# Driver_Controller.net
KiCad netlist of a schematic drawn in Altium Designer
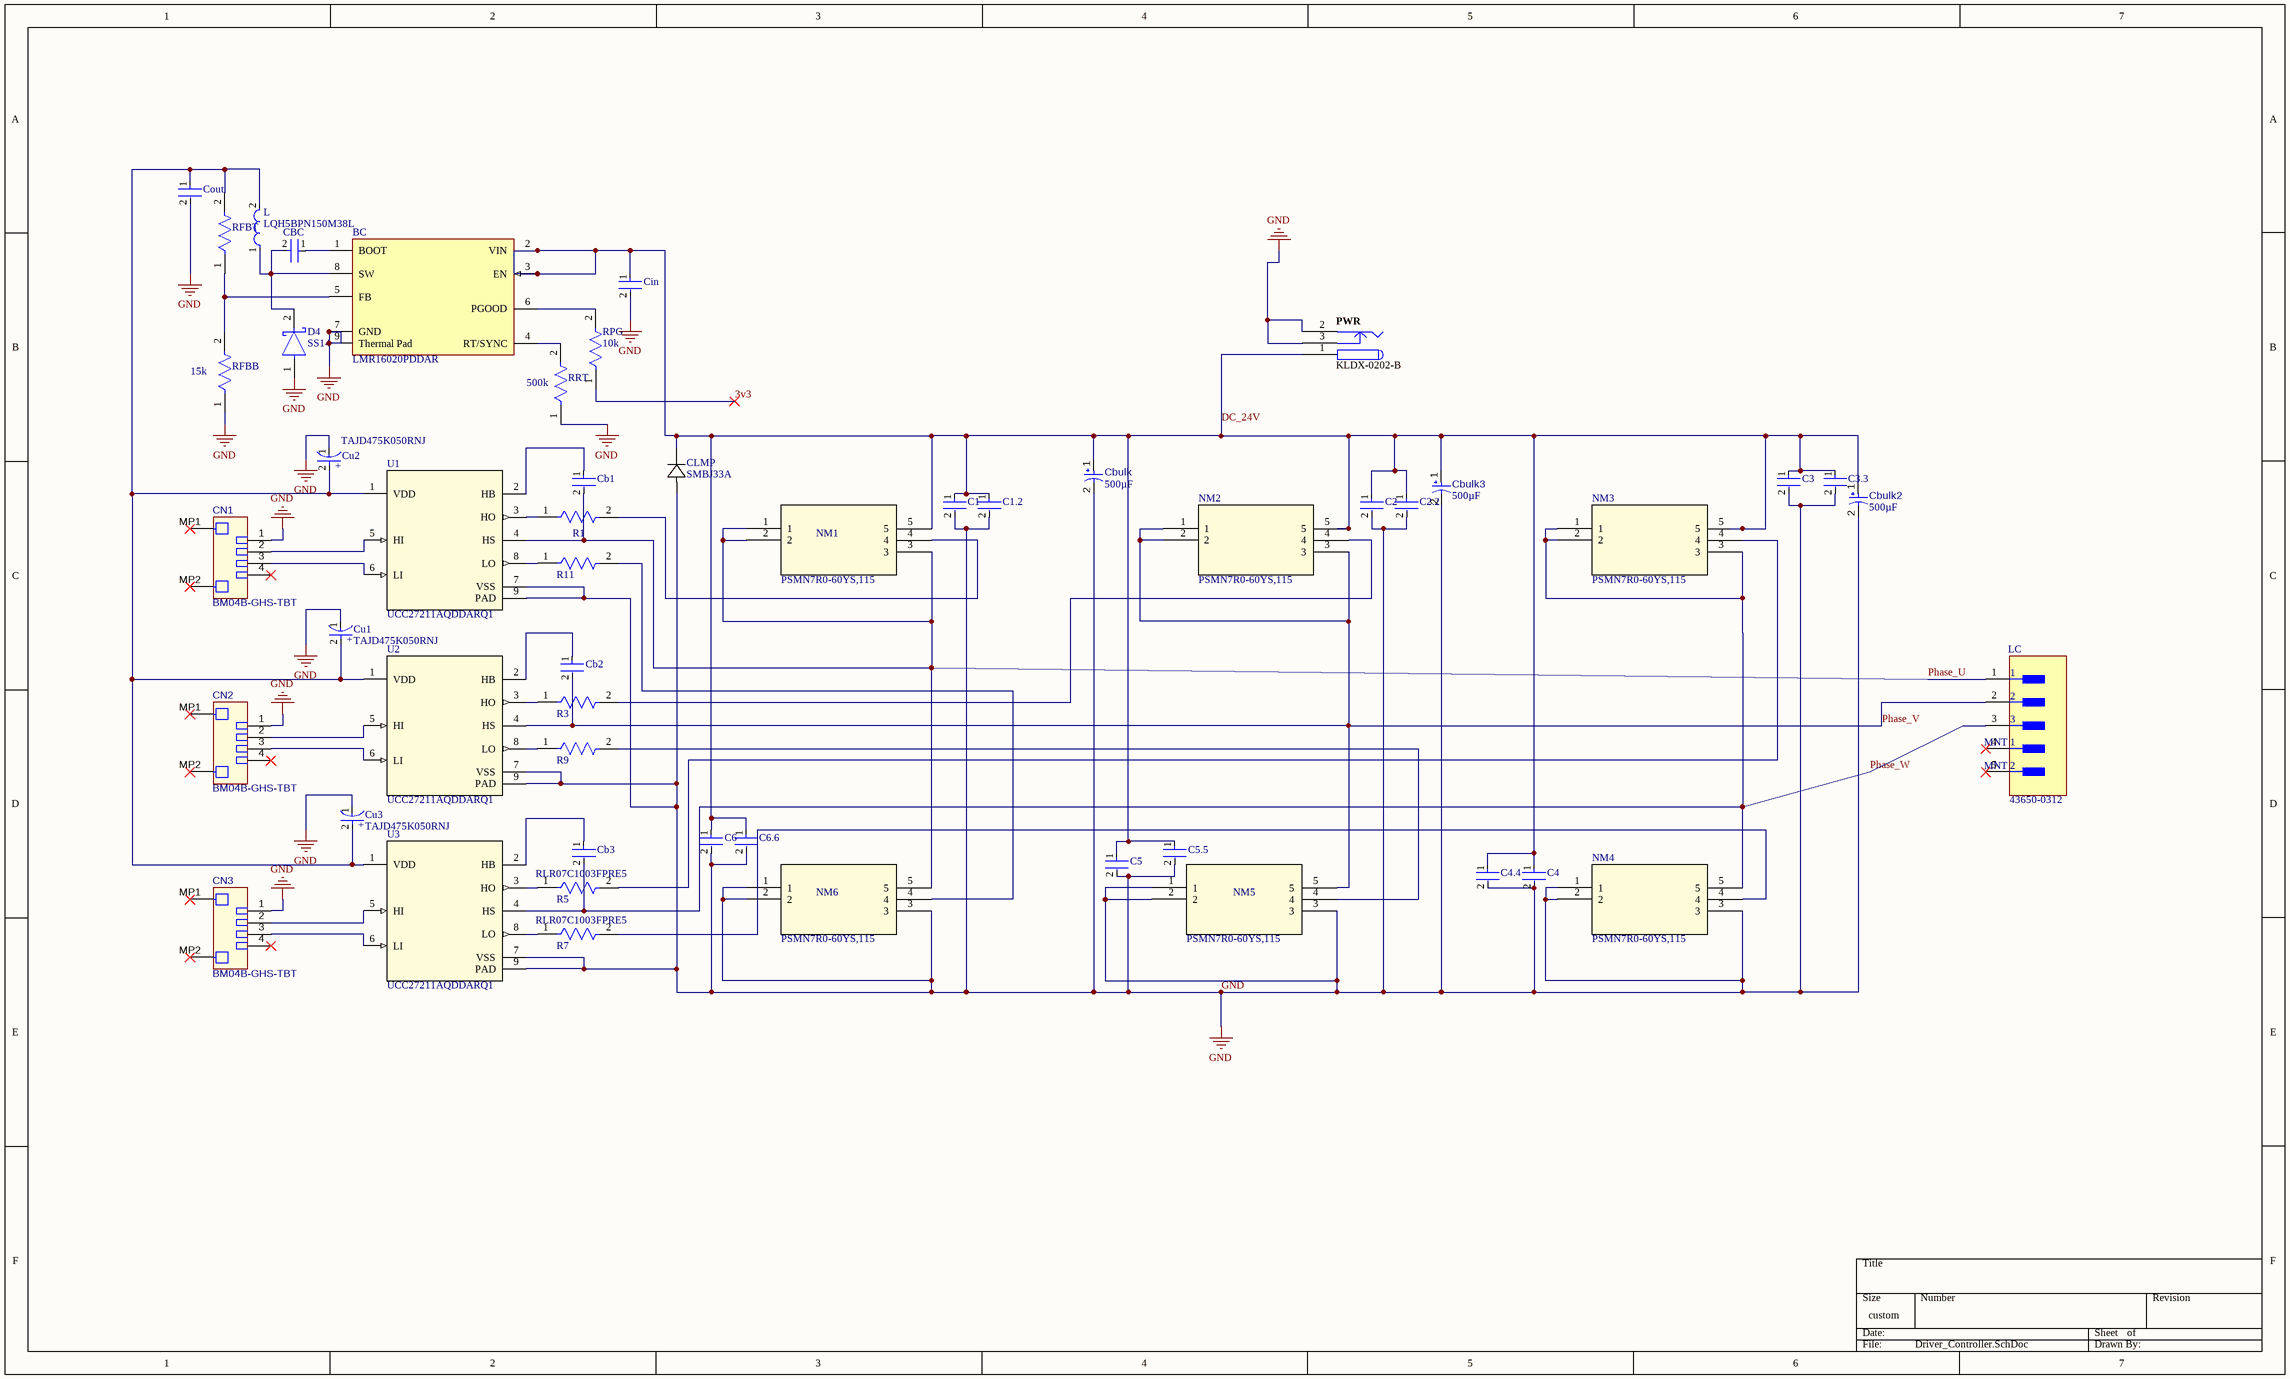
[diagram p0: Driver_Controller.SchDoc]

(export (version "E")
  (design (tool "Eeschema 10.0.6"))
  (components
    (comp (ref "BC")
      (value "LMR16020PDDAR")
      (footprint "FP-DDA0008E-MFG")
      (description "IC REG BUCK ADJUSTABLE 2A 8SOPWR")
      (fields
        (field (name "OCTOPART") "https://octopart.com/lmr16020pddar-texas+instruments-70110951")
        (field (name "MANUFACTURER") "Texas Instruments")
      )
      (libsource (lib "Altium Content Vault") (part "f39d125abe64159f813db9a9ec740f7"))
    )
    (comp (ref "C1")
      (value "RCER72A104K1K1H03B")
      (footprint "FP-RCE1K1-2_5-MFG")
      (description "1uF")
      (fields (field (name "TOLERANCE") "10%"))
      (libsource (lib "") (part "02cd4be3c70576c341d710602a673aa_1"))
    )
    (comp (ref "C1.2")
      (value "RCER72A104K1K1H03B")
      (footprint "FP-RCE1K1-2_5-MFG")
      (description "Cap Ceramic Monolithic 100nF 100V 10% Thru-Hole Bulk")
      (fields (field (name "TOLERANCE") "10%"))
      (libsource (lib "") (part "02cd4be3c70576c341d710602a673aa_1"))
    )
    (comp (ref "C2")
      (value "RCER72A104K1K1H03B")
      (footprint "FP-RCE1K1-2_5-MFG")
      (description "Cap Ceramic Monolithic 100nF 100V 10% Thru-Hole Bulk")
      (fields (field (name "TOLERANCE") "10%"))
      (libsource (lib "") (part "02cd4be3c70576c341d710602a673aa_1"))
    )
    (comp (ref "C2.2")
      (value "RCER72A104K1K1H03B")
      (footprint "FP-RCE1K1-2_5-MFG")
      (description "Cap Ceramic Monolithic 100nF 100V 10% Thru-Hole Bulk")
      (fields (field (name "TOLERANCE") "10%"))
      (libsource (lib "") (part "02cd4be3c70576c341d710602a673aa_1"))
    )
    (comp (ref "C3")
      (value "RCER72A104K1K1H03B")
      (footprint "FP-RCE1K1-2_5-MFG")
      (description "Cap Ceramic Monolithic 100nF 100V 10% Thru-Hole Bulk")
      (fields (field (name "TOLERANCE") "10%"))
      (libsource (lib "") (part "02cd4be3c70576c341d710602a673aa_1"))
    )
    (comp (ref "C3.3")
      (value "RCER72A104K1K1H03B")
      (footprint "FP-RCE1K1-2_5-MFG")
      (description "Cap Ceramic Monolithic 100nF 100V 10% Thru-Hole Bulk")
      (fields (field (name "TOLERANCE") "10%"))
      (libsource (lib "") (part "02cd4be3c70576c341d710602a673aa_1"))
    )
    (comp (ref "C4")
      (value "RCER72A104K1K1H03B")
      (footprint "FP-RCE1K1-2_5-MFG")
      (description "Cap Ceramic Monolithic 100nF 100V 10% Thru-Hole Bulk")
      (fields (field (name "TOLERANCE") "10%"))
      (libsource (lib "") (part "02cd4be3c70576c341d710602a673aa_1"))
    )
    (comp (ref "C4.4")
      (value "RCER72A104K1K1H03B")
      (footprint "FP-RCE1K1-2_5-MFG")
      (description "Cap Ceramic Monolithic 100nF 100V 10% Thru-Hole Bulk")
      (fields (field (name "TOLERANCE") "10%"))
      (libsource (lib "") (part "02cd4be3c70576c341d710602a673aa_1"))
    )
    (comp (ref "C5")
      (value "RCER72A104K1K1H03B")
      (footprint "FP-RCE1K1-2_5-MFG")
      (description "Cap Ceramic Monolithic 100nF 100V 10% Thru-Hole Bulk")
      (fields (field (name "TOLERANCE") "10%"))
      (libsource (lib "") (part "02cd4be3c70576c341d710602a673aa_1"))
    )
    (comp (ref "C5.5")
      (value "RCER72A104K1K1H03B")
      (footprint "FP-RCE1K1-2_5-MFG")
      (description "Cap Ceramic Monolithic 100nF 100V 10% Thru-Hole Bulk")
      (fields (field (name "TOLERANCE") "10%"))
      (libsource (lib "") (part "02cd4be3c70576c341d710602a673aa_1"))
    )
    (comp (ref "C6")
      (value "RCER72A104K1K1H03B")
      (footprint "FP-RCE1K1-2_5-MFG")
      (description "Cap Ceramic Monolithic 100nF 100V 10% Thru-Hole Bulk")
      (fields (field (name "TOLERANCE") "10%"))
      (libsource (lib "") (part "02cd4be3c70576c341d710602a673aa_1"))
    )
    (comp (ref "C6.6")
      (value "RCER72A104K1K1H03B")
      (footprint "FP-RCE1K1-2_5-MFG")
      (description "Cap Ceramic Monolithic 100nF 100V 10% Thru-Hole Bulk")
      (fields (field (name "TOLERANCE") "10%"))
      (libsource (lib "") (part "02cd4be3c70576c341d710602a673aa_1"))
    )
    (comp (ref "Cb1")
      (value "RCER72A104K1K1H03B")
      (footprint "FP-RCE1K1-2_5-MFG")
      (description "0.22uF")
      (fields (field (name "TOLERANCE") "10%"))
      (libsource (lib "") (part "02cd4be3c70576c341d710602a673aa_1"))
    )
    (comp (ref "Cb2")
      (value "RCER72A104K1K1H03B")
      (footprint "FP-RCE1K1-2_5-MFG")
      (description "Cap Ceramic Monolithic 100nF 100V 10% Thru-Hole Bulk")
      (fields (field (name "TOLERANCE") "10%"))
      (libsource (lib "") (part "02cd4be3c70576c341d710602a673aa_1"))
    )
    (comp (ref "Cb3")
      (value "RCER72A104K1K1H03B")
      (footprint "FP-RCE1K1-2_5-MFG")
      (description "Cap Ceramic Monolithic 100nF 100V 10% Thru-Hole Bulk")
      (fields (field (name "TOLERANCE") "10%"))
      (libsource (lib "") (part "02cd4be3c70576c341d710602a673aa_1"))
    )
    (comp (ref "CBC")
      (value "RCER72A104K1K1H03B")
      (footprint "FP-RCE1K1-2_5-MFG")
      (description "0.1 uF cermaic")
      (fields (field (name "TOLERANCE") "10%"))
      (libsource (lib "Altium Content Vault") (part "02cd4be3c70576c341d710602a673aa"))
    )
    (comp (ref "Cbulk")
      (value "500µF")
      (footprint "CAPPR55-200-1100X500X1200")
      (description "220 uF electrolytic capacitor 50V")
      (fields (field (name "TOLERANCE") "20%") (field (name "MANUFACTURER") "Panasonic"))
      (libsource (lib "St121903 St121903") (part "CAP-P-2"))
    )
    (comp (ref "Cbulk2")
      (value "500µF")
      (footprint "CAPPR55-200-1100X500X1200")
      (description "Aluminum Electrolytic Capacitor, 2.2 uF, +/- 20%, 50 V, -40 to 85 degC, 2-Pin THD, RoHS, Bulk")
      (fields (field (name "TOLERANCE") "20%") (field (name "MANUFACTURER") "Panasonic"))
      (libsource (lib "St121903 St121903") (part "CAP-P-2"))
    )
    (comp (ref "Cbulk3")
      (value "500µF")
      (footprint "CAPPR55-200-1100X500X1200")
      (description "Aluminum Electrolytic Capacitor, 2.2 uF, +/- 20%, 50 V, -40 to 85 degC, 2-Pin THD, RoHS, Bulk")
      (fields (field (name "TOLERANCE") "20%") (field (name "MANUFACTURER") "Panasonic"))
      (libsource (lib "St121903 St121903") (part "CAP-P-2"))
    )
    (comp (ref "Cin")
      (value "RCER72A104K1K1H03B")
      (footprint "FP-RCE1K1-2_5-MFG")
      (description "10uF")
      (fields (field (name "TOLERANCE") "10%"))
      (libsource (lib "") (part "02cd4be3c70576c341d710602a673aa_1"))
    )
    (comp (ref "CLMP")
      (value "SMBJ33A")
      (footprint "SMB")
      (description "No Description Available")
      (fields (field (name "COPYRIGHT") "Copyright (C) 2025 Ultra Librarian. All rights reserved."))
      (libsource (lib "SMBJ33A") (part "SMBJ33A"))
    )
    (comp (ref "CN1")
      (value "BM04B-GHS-TBT")
      (footprint "JST-BM04B-GHS-TBT_V")
      (description "Header, Pitch 1.25 mm, 1 x 4 Position, Height 4.05 mm, -25 to 85 degC")
      (libsource (lib "St121903 St121903") (part "CMP-00071-3"))
    )
    (comp (ref "CN2")
      (value "BM04B-GHS-TBT")
      (footprint "JST-BM04B-GHS-TBT_V")
      (description "Header, Pitch 1.25 mm, 1 x 4 Position, Height 4.05 mm, -25 to 85 degC")
      (libsource (lib "St121903 St121903") (part "CMP-00071-3"))
    )
    (comp (ref "CN3")
      (value "BM04B-GHS-TBT")
      (footprint "JST-BM04B-GHS-TBT_V")
      (description "Header, Pitch 1.25 mm, 1 x 4 Position, Height 4.05 mm, -25 to 85 degC")
      (libsource (lib "St121903 St121903") (part "CMP-00071-3"))
    )
    (comp (ref "Cout")
      (value "RCER72A104K1K1H03B")
      (footprint "FP-RCE1K1-2_5-MFG")
      (description "47 uF cap")
      (fields (field (name "TOLERANCE") "10%"))
      (libsource (lib "") (part "02cd4be3c70576c341d710602a673aa_1"))
    )
    (comp (ref "Cu1")
      (value "TAJD475K050RNJ")
      (footprint "FP-TAJD-MFG")
      (description "4.7uF 50V  ±10% 1.4Ω 2917  SMD Tantalum Capacitor")
      (fields (field (name "TOLERANCE") "10%") (field (name "VOLTAGE") "50V"))
      (libsource (lib "Altium Content Vault") (part "a00bbbee19879c290e62620ae7e47b1"))
    )
    (comp (ref "Cu2")
      (value "TAJD475K050RNJ")
      (footprint "FP-TAJD-MFG")
      (description "4.7uF 50V  ±10% 1.4Ω 2917  SMD Tantalum Capacitor")
      (fields (field (name "TOLERANCE") "10%") (field (name "VOLTAGE") "50V"))
      (libsource (lib "Altium Content Vault") (part "a00bbbee19879c290e62620ae7e47b1"))
    )
    (comp (ref "Cu3")
      (value "TAJD475K050RNJ")
      (footprint "FP-TAJD-MFG")
      (description "4.7uF 50V  ±10% 1.4Ω 2917  SMD Tantalum Capacitor")
      (fields (field (name "TOLERANCE") "10%") (field (name "VOLTAGE") "50V"))
      (libsource (lib "Altium Content Vault") (part "a00bbbee19879c290e62620ae7e47b1"))
    )
    (comp (ref "D4")
      (value "SS14")
      (footprint "FP-403AE-MFG")
      (description "DIODE SCHOTTKY 40V 1A SMA")
      (fields
        (field (name "MANUFACTURER") "ON Semiconductor")
        (field (name "OCTOPART") "https://octopart.com/ss14-on+semiconductor-29205033")
      )
      (libsource (lib "Altium Content Vault") (part "360ad2f4ac25a952324d13796385471"))
    )
    (comp (ref "L")
      (value "LQH5BPN150M38L")
      (footprint "FP-LQH5BPN_38-MFG")
      (description "Wire Wound Ferrite Inductor for Power Lines 15μH ±20% 0.096Ω 1900mA 2020")
      (libsource (lib "Altium Content Vault") (part "725321dda6339637d4d059423bc1c3c"))
    )
    (comp (ref "LC")
      (value "43650-0312")
      (footprint "FP-43650-0312-MFG")
      (description "CONN HEADER SMD R/A 3POS 3MM")
      (fields
        (field (name "MANUFACTURER") "Molex")
        (field (name "OCTOPART") "https://octopart.com/43650-0312-molex-298103")
      )
      (libsource (lib "Altium Content Vault") (part "793d9f4ef75ba7bed6a6e310629fedb"))
    )
    (comp (ref "NM1")
      (value "PSMN7R0-60YS,115")
      (footprint "IC5_PSMN7R0-60YS,115_NEX-L")
      (description "No Description Available")
      (fields (field (name "COPYRIGHT") "Copyright (C) 2025 Ultra Librarian. All rights reserved."))
      (libsource (lib "PSMN7R0-60YS,115") (part "PSMN7R0-60YS,115"))
    )
    (comp (ref "NM2")
      (value "PSMN7R0-60YS,115")
      (footprint "IC5_PSMN7R0-60YS,115_NEX-L")
      (description "No Description Available")
      (fields (field (name "COPYRIGHT") "Copyright (C) 2025 Ultra Librarian. All rights reserved."))
      (libsource (lib "PSMN7R0-60YS,115") (part "PSMN7R0-60YS,115"))
    )
    (comp (ref "NM3")
      (value "PSMN7R0-60YS,115")
      (footprint "IC5_PSMN7R0-60YS,115_NEX-L")
      (description "No Description Available")
      (fields (field (name "COPYRIGHT") "Copyright (C) 2025 Ultra Librarian. All rights reserved."))
      (libsource (lib "PSMN7R0-60YS,115") (part "PSMN7R0-60YS,115"))
    )
    (comp (ref "NM4")
      (value "PSMN7R0-60YS,115")
      (footprint "IC5_PSMN7R0-60YS,115_NEX-L")
      (description "No Description Available")
      (fields (field (name "COPYRIGHT") "Copyright (C) 2025 Ultra Librarian. All rights reserved."))
      (libsource (lib "PSMN7R0-60YS,115") (part "PSMN7R0-60YS,115"))
    )
    (comp (ref "NM5")
      (value "PSMN7R0-60YS,115")
      (footprint "IC5_PSMN7R0-60YS,115_NEX-L")
      (description "No Description Available")
      (fields (field (name "COPYRIGHT") "Copyright (C) 2025 Ultra Librarian. All rights reserved."))
      (libsource (lib "PSMN7R0-60YS,115") (part "PSMN7R0-60YS,115"))
    )
    (comp (ref "NM6")
      (value "PSMN7R0-60YS,115")
      (footprint "IC5_PSMN7R0-60YS,115_NEX-L")
      (description "No Description Available")
      (fields (field (name "COPYRIGHT") "Copyright (C) 2025 Ultra Librarian. All rights reserved."))
      (libsource (lib "PSMN7R0-60YS,115") (part "PSMN7R0-60YS,115"))
    )
    (comp (ref "PWR")
      (value "KLDX-0202-B")
      (footprint "KYCN-KLDX-0202-B_V")
      (description "3 Conductor Power Jack, 2 break 2 aux contacts")
      (libsource (lib "Altium Content Vault") (part "KYCN-KLDX-0202-B-3"))
    )
    (comp (ref "R1")
      (value "RLR07C1003FPRE5")
      (footprint "FP-RLR07-MFG")
      (description "RLR07C1003FPRE5 Resistor, 100 kOhm, ± 1%, 250 mW, Axial Leaded, Metal Film, Military Reliability")
      (fields (field (name "TOLERANCE") "1%"))
      (libsource (lib "Altium Content Vault") (part "1029c3af85768c4190bb7ad29bc67b5"))
    )
    (comp (ref "R3")
      (value "RLR07C1003FPRE5")
      (footprint "FP-RLR07-MFG")
      (description "RLR07C1003FPRE5 Resistor, 100 kOhm, ± 1%, 250 mW, Axial Leaded, Metal Film, Military Reliability")
      (fields (field (name "TOLERANCE") "1%"))
      (libsource (lib "Altium Content Vault") (part "1029c3af85768c4190bb7ad29bc67b5"))
    )
    (comp (ref "R5")
      (value "RLR07C1003FPRE5")
      (footprint "FP-RLR07-MFG")
      (description "RLR07C1003FPRE5 Resistor, 100 kOhm, ± 1%, 250 mW, Axial Leaded, Metal Film, Military Reliability")
      (fields (field (name "TOLERANCE") "1%"))
      (libsource (lib "Altium Content Vault") (part "1029c3af85768c4190bb7ad29bc67b5"))
    )
    (comp (ref "R7")
      (value "RLR07C1003FPRE5")
      (footprint "FP-RLR07-MFG")
      (description "RLR07C1003FPRE5 Resistor, 100 kOhm, ± 1%, 250 mW, Axial Leaded, Metal Film, Military Reliability")
      (fields (field (name "TOLERANCE") "1%"))
      (libsource (lib "Altium Content Vault") (part "1029c3af85768c4190bb7ad29bc67b5"))
    )
    (comp (ref "R9")
      (value "RLR07C1003FPRE5")
      (footprint "FP-RLR07-MFG")
      (description "RLR07C1003FPRE5 Resistor, 100 kOhm, ± 1%, 250 mW, Axial Leaded, Metal Film, Military Reliability")
      (fields (field (name "TOLERANCE") "1%"))
      (libsource (lib "Altium Content Vault") (part "1029c3af85768c4190bb7ad29bc67b5"))
    )
    (comp (ref "R11")
      (value "RLR07C1003FPRE5")
      (footprint "FP-RLR07-MFG")
      (description "10")
      (fields (field (name "TOLERANCE") "1%"))
      (libsource (lib "Altium Content Vault") (part "1029c3af85768c4190bb7ad29bc67b5"))
    )
    (comp (ref "RFBB")
      (value "15k")
      (footprint "FP-RLR07-MFG")
      (description "RLR07C1003FPRE5 Resistor, 100 kOhm, ± 1%, 250 mW, Axial Leaded, Metal Film, Military Reliability")
      (fields (field (name "TOLERANCE") "1%"))
      (libsource (lib "Altium Content Vault") (part "1029c3af85768c4190bb7ad29bc67b5"))
    )
    (comp (ref "RFBT")
      (value "150k")
      (footprint "FP-RLR07-MFG")
      (description "RLR07C1003FPRE5 Resistor, 100 kOhm, ± 1%, 250 mW, Axial Leaded, Metal Film, Military Reliability")
      (fields (field (name "TOLERANCE") "1%"))
      (libsource (lib "Altium Content Vault") (part "1029c3af85768c4190bb7ad29bc67b5"))
    )
    (comp (ref "RPG")
      (value "10k")
      (footprint "FP-RLR07-MFG")
      (description "RLR07C1003FPRE5 Resistor, 100 kOhm, ± 1%, 250 mW, Axial Leaded, Metal Film, Military Reliability")
      (fields (field (name "TOLERANCE") "1%"))
      (libsource (lib "Altium Content Vault") (part "1029c3af85768c4190bb7ad29bc67b5"))
    )
    (comp (ref "RRT")
      (value "500k")
      (footprint "FP-RLR07-MFG")
      (description "RLR07C1003FPRE5 Resistor, 100 kOhm, ± 1%, 250 mW, Axial Leaded, Metal Film, Military Reliability")
      (fields (field (name "TOLERANCE") "1%"))
      (libsource (lib "Altium Content Vault") (part "1029c3af85768c4190bb7ad29bc67b5"))
    )
    (comp (ref "U1")
      (value "UCC27211AQDDARQ1")
      (footprint "DDA0008E_N")
      (fields (field (name "COPYRIGHT") "Copyright (C) 2025 Ultra Librarian. All rights reserved."))
      (libsource (lib "UCC27211AQDDARQ1") (part "UCC27211AQDDARQ1"))
    )
    (comp (ref "U2")
      (value "UCC27211AQDDARQ1")
      (footprint "DDA0008E_N")
      (fields (field (name "COPYRIGHT") "Copyright (C) 2025 Ultra Librarian. All rights reserved."))
      (libsource (lib "UCC27211AQDDARQ1") (part "UCC27211AQDDARQ1"))
    )
    (comp (ref "U3")
      (value "UCC27211AQDDARQ1")
      (footprint "DDA0008E_N")
      (fields (field (name "COPYRIGHT") "Copyright (C) 2025 Ultra Librarian. All rights reserved."))
      (libsource (lib "UCC27211AQDDARQ1") (part "UCC27211AQDDARQ1"))
    )
  )
  (nets
    (net (code "1") (name "/3v3") (class "Default")
      (node (ref "RPG") (pin "1") (pinfunction "1_1") (pintype "passive+no_connect"))
    )
    (net (code "2") (name "/DC_24V") (class "Default")
      (node (ref "BC") (pin "2") (pinfunction "VIN_2") (pintype "power_in"))
      (node (ref "BC") (pin "3") (pinfunction "EN_3") (pintype "input"))
      (node (ref "C1") (pin "1") (pinfunction "1_1") (pintype "passive"))
      (node (ref "C1.2") (pin "1") (pinfunction "1_1") (pintype "passive"))
      (node (ref "C2") (pin "1") (pinfunction "1_1") (pintype "passive"))
      (node (ref "C2.2") (pin "1") (pinfunction "1_1") (pintype "passive"))
      (node (ref "C3") (pin "1") (pinfunction "1_1") (pintype "passive"))
      (node (ref "C3.3") (pin "1") (pinfunction "1_1") (pintype "passive"))
      (node (ref "C4") (pin "1") (pinfunction "1_1") (pintype "passive"))
      (node (ref "C4.4") (pin "1") (pinfunction "1_1") (pintype "passive"))
      (node (ref "C5") (pin "1") (pinfunction "1_1") (pintype "passive"))
      (node (ref "C5.5") (pin "1") (pinfunction "1_1") (pintype "passive"))
      (node (ref "C6") (pin "1") (pinfunction "1_1") (pintype "passive"))
      (node (ref "C6.6") (pin "1") (pinfunction "1_1") (pintype "passive"))
      (node (ref "CLMP") (pin "1") (pinfunction "1_1") (pintype "passive"))
      (node (ref "Cbulk") (pin "1") (pinfunction "1_1") (pintype "passive"))
      (node (ref "Cbulk2") (pin "1") (pinfunction "1_1") (pintype "passive"))
      (node (ref "Cbulk3") (pin "1") (pinfunction "1_1") (pintype "passive"))
      (node (ref "Cin") (pin "1") (pinfunction "1_1") (pintype "passive"))
      (node (ref "NM1") (pin "5") (pinfunction "5_5") (pintype "passive"))
      (node (ref "NM2") (pin "5") (pinfunction "5_5") (pintype "passive"))
      (node (ref "NM3") (pin "5") (pinfunction "5_5") (pintype "passive"))
      (node (ref "PWR") (pin "1") (pintype "power_in"))
    )
    (net (code "3") (name "/Phase_U") (class "Default")
      (node (ref "Cb1") (pin "2") (pinfunction "2_2") (pintype "passive"))
      (node (ref "LC") (pin "1") (pinfunction "1_1") (pintype "passive"))
      (node (ref "NM1") (pin "1") (pinfunction "1_1") (pintype "passive"))
      (node (ref "NM1") (pin "2") (pinfunction "2_2") (pintype "passive"))
      (node (ref "NM1") (pin "3") (pinfunction "3_3") (pintype "passive"))
      (node (ref "NM6") (pin "5") (pinfunction "5_5") (pintype "passive"))
      (node (ref "U1") (pin "4") (pinfunction "HS_4") (pintype "power_in"))
    )
    (net (code "4") (name "/Phase_V") (class "Default")
      (node (ref "Cb2") (pin "2") (pinfunction "2_2") (pintype "passive"))
      (node (ref "LC") (pin "2") (pinfunction "2_2") (pintype "passive"))
      (node (ref "NM2") (pin "1") (pinfunction "1_1") (pintype "passive"))
      (node (ref "NM2") (pin "2") (pinfunction "2_2") (pintype "passive"))
      (node (ref "NM2") (pin "3") (pinfunction "3_3") (pintype "passive"))
      (node (ref "NM5") (pin "5") (pinfunction "5_5") (pintype "passive"))
      (node (ref "U2") (pin "4") (pinfunction "HS_4") (pintype "power_in"))
    )
    (net (code "5") (name "/Phase_W") (class "Default")
      (node (ref "Cb3") (pin "2") (pinfunction "2_2") (pintype "passive"))
      (node (ref "LC") (pin "3") (pinfunction "3_3") (pintype "passive"))
      (node (ref "NM3") (pin "1") (pinfunction "1_1") (pintype "passive"))
      (node (ref "NM3") (pin "2") (pinfunction "2_2") (pintype "passive"))
      (node (ref "NM3") (pin "3") (pinfunction "3_3") (pintype "passive"))
      (node (ref "NM4") (pin "5") (pinfunction "5_5") (pintype "passive"))
      (node (ref "U3") (pin "4") (pinfunction "HS_4") (pintype "power_in"))
    )
    (net (code "6") (name "GND") (class "Default")
      (node (ref "BC") (pin "7") (pinfunction "GND_7") (pintype "power_in"))
      (node (ref "BC") (pin "9") (pinfunction "Thermal_Pad_9") (pintype "power_in"))
      (node (ref "C1") (pin "2") (pinfunction "2_2") (pintype "passive"))
      (node (ref "C1.2") (pin "2") (pinfunction "2_2") (pintype "passive"))
      (node (ref "C2") (pin "2") (pinfunction "2_2") (pintype "passive"))
      (node (ref "C2.2") (pin "2") (pinfunction "2_2") (pintype "passive"))
      (node (ref "C3") (pin "2") (pinfunction "2_2") (pintype "passive"))
      (node (ref "C3.3") (pin "2") (pinfunction "2_2") (pintype "passive"))
      (node (ref "C4") (pin "2") (pinfunction "2_2") (pintype "passive"))
      (node (ref "C4.4") (pin "2") (pinfunction "2_2") (pintype "passive"))
      (node (ref "C5") (pin "2") (pinfunction "2_2") (pintype "passive"))
      (node (ref "C5.5") (pin "2") (pinfunction "2_2") (pintype "passive"))
      (node (ref "C6") (pin "2") (pinfunction "2_2") (pintype "passive"))
      (node (ref "C6.6") (pin "2") (pinfunction "2_2") (pintype "passive"))
      (node (ref "CLMP") (pin "2") (pinfunction "2_2") (pintype "passive"))
      (node (ref "CN1") (pin "1") (pinfunction "1_1") (pintype "passive"))
      (node (ref "CN2") (pin "1") (pinfunction "1_1") (pintype "passive"))
      (node (ref "CN3") (pin "1") (pinfunction "1_1") (pintype "passive"))
      (node (ref "Cbulk") (pin "2") (pinfunction "2_2") (pintype "passive"))
      (node (ref "Cbulk2") (pin "2") (pinfunction "2_2") (pintype "passive"))
      (node (ref "Cbulk3") (pin "2") (pinfunction "2_2") (pintype "passive"))
      (node (ref "Cin") (pin "2") (pinfunction "2_2") (pintype "passive"))
      (node (ref "Cout") (pin "2") (pinfunction "2_2") (pintype "passive"))
      (node (ref "Cu1") (pin "1") (pinfunction "C_1") (pintype "passive"))
      (node (ref "Cu2") (pin "1") (pinfunction "C_1") (pintype "passive"))
      (node (ref "Cu3") (pin "1") (pinfunction "C_1") (pintype "passive"))
      (node (ref "D4") (pin "1") (pinfunction "A_1") (pintype "passive"))
      (node (ref "NM4") (pin "1") (pinfunction "1_1") (pintype "passive"))
      (node (ref "NM4") (pin "2") (pinfunction "2_2") (pintype "passive"))
      (node (ref "NM4") (pin "3") (pinfunction "3_3") (pintype "passive"))
      (node (ref "NM5") (pin "1") (pinfunction "1_1") (pintype "passive"))
      (node (ref "NM5") (pin "2") (pinfunction "2_2") (pintype "passive"))
      (node (ref "NM5") (pin "3") (pinfunction "3_3") (pintype "passive"))
      (node (ref "NM6") (pin "1") (pinfunction "1_1") (pintype "passive"))
      (node (ref "NM6") (pin "2") (pinfunction "2_2") (pintype "passive"))
      (node (ref "NM6") (pin "3") (pinfunction "3_3") (pintype "passive"))
      (node (ref "PWR") (pin "2") (pintype "power_in"))
      (node (ref "PWR") (pin "3") (pintype "power_in"))
      (node (ref "RFBB") (pin "1") (pinfunction "1_1") (pintype "passive"))
      (node (ref "RRT") (pin "1") (pinfunction "1_1") (pintype "passive"))
      (node (ref "U1") (pin "7") (pinfunction "VSS_7") (pintype "power_in"))
      (node (ref "U1") (pin "9") (pinfunction "PAD_9") (pintype "passive"))
      (node (ref "U2") (pin "7") (pinfunction "VSS_7") (pintype "power_in"))
      (node (ref "U2") (pin "9") (pinfunction "PAD_9") (pintype "passive"))
      (node (ref "U3") (pin "7") (pinfunction "VSS_7") (pintype "power_in"))
      (node (ref "U3") (pin "9") (pinfunction "PAD_9") (pintype "passive"))
    )
    (net (code "7") (name "Net-(BC-BOOT)") (class "Default")
      (node (ref "BC") (pin "1") (pinfunction "BOOT_1") (pintype "passive"))
      (node (ref "CBC") (pin "1") (pinfunction "1_1") (pintype "passive"))
    )
    (net (code "8") (name "Net-(BC-FB)") (class "Default")
      (node (ref "BC") (pin "5") (pinfunction "FB_5") (pintype "passive"))
      (node (ref "RFBB") (pin "2") (pinfunction "2_2") (pintype "passive"))
      (node (ref "RFBT") (pin "1") (pinfunction "1_1") (pintype "passive"))
    )
    (net (code "9") (name "Net-(BC-PGOOD)") (class "Default")
      (node (ref "BC") (pin "6") (pinfunction "PGOOD_6") (pintype "open_collector"))
      (node (ref "RPG") (pin "2") (pinfunction "2_2") (pintype "passive"))
    )
    (net (code "10") (name "Net-(BC-RT{slash}SYNC)") (class "Default")
      (node (ref "BC") (pin "4") (pinfunction "RT/SYNC_4") (pintype "passive"))
      (node (ref "RRT") (pin "2") (pinfunction "2_2") (pintype "passive"))
    )
    (net (code "11") (name "Net-(BC-SW)") (class "Default")
      (node (ref "BC") (pin "8") (pinfunction "SW_8") (pintype "passive"))
      (node (ref "CBC") (pin "2") (pinfunction "2_2") (pintype "passive"))
      (node (ref "D4") (pin "2") (pinfunction "C_2") (pintype "passive"))
      (node (ref "L") (pin "1") (pinfunction "1_1") (pintype "passive"))
    )
    (net (code "12") (name "Net-(Cu1-A)") (class "Default")
      (node (ref "Cout") (pin "1") (pinfunction "1_1") (pintype "passive"))
      (node (ref "Cu1") (pin "2") (pinfunction "A_2") (pintype "passive"))
      (node (ref "Cu2") (pin "2") (pinfunction "A_2") (pintype "passive"))
      (node (ref "Cu3") (pin "2") (pinfunction "A_2") (pintype "passive"))
      (node (ref "L") (pin "2") (pinfunction "2_2") (pintype "passive"))
      (node (ref "RFBT") (pin "2") (pinfunction "2_2") (pintype "passive"))
      (node (ref "U1") (pin "1") (pinfunction "VDD_1") (pintype "power_in"))
      (node (ref "U2") (pin "1") (pinfunction "VDD_1") (pintype "power_in"))
      (node (ref "U3") (pin "1") (pinfunction "VDD_1") (pintype "power_in"))
    )
    (net (code "13") (name "Net-(NM1-Pad4)") (class "Default")
      (node (ref "NM1") (pin "4") (pinfunction "4_4") (pintype "passive"))
      (node (ref "R1") (pin "2") (pinfunction "2_2") (pintype "passive"))
    )
    (net (code "14") (name "Net-(NM2-Pad4)") (class "Default")
      (node (ref "NM2") (pin "4") (pinfunction "4_4") (pintype "passive"))
      (node (ref "R3") (pin "2") (pinfunction "2_2") (pintype "passive"))
    )
    (net (code "15") (name "Net-(NM3-Pad4)") (class "Default")
      (node (ref "NM3") (pin "4") (pinfunction "4_4") (pintype "passive"))
      (node (ref "R5") (pin "2") (pinfunction "2_2") (pintype "passive"))
    )
    (net (code "16") (name "Net-(NM4-Pad4)") (class "Default")
      (node (ref "NM4") (pin "4") (pinfunction "4_4") (pintype "passive"))
      (node (ref "R7") (pin "2") (pinfunction "2_2") (pintype "passive"))
    )
    (net (code "17") (name "Net-(NM5-Pad4)") (class "Default")
      (node (ref "NM5") (pin "4") (pinfunction "4_4") (pintype "passive"))
      (node (ref "R9") (pin "2") (pinfunction "2_2") (pintype "passive"))
    )
    (net (code "18") (name "Net-(NM6-Pad4)") (class "Default")
      (node (ref "NM6") (pin "4") (pinfunction "4_4") (pintype "passive"))
      (node (ref "R11") (pin "2") (pinfunction "2_2") (pintype "passive"))
    )
    (net (code "19") (name "Net-(U1-HB)") (class "Default")
      (node (ref "Cb1") (pin "1") (pinfunction "1_1") (pintype "passive"))
      (node (ref "U1") (pin "2") (pinfunction "HB_2") (pintype "power_in"))
    )
    (net (code "20") (name "Net-(U1-HI)") (class "Default")
      (node (ref "CN1") (pin "2") (pinfunction "2_2") (pintype "passive"))
      (node (ref "U1") (pin "5") (pinfunction "HI_5") (pintype "input"))
    )
    (net (code "21") (name "Net-(U1-HO)") (class "Default")
      (node (ref "R1") (pin "1") (pinfunction "1_1") (pintype "passive"))
      (node (ref "U1") (pin "3") (pinfunction "HO_3") (pintype "output"))
    )
    (net (code "22") (name "Net-(U1-LI)") (class "Default")
      (node (ref "CN1") (pin "3") (pinfunction "3_3") (pintype "passive"))
      (node (ref "U1") (pin "6") (pinfunction "LI_6") (pintype "input"))
    )
    (net (code "23") (name "Net-(U1-LO)") (class "Default")
      (node (ref "R11") (pin "1") (pinfunction "1_1") (pintype "passive"))
      (node (ref "U1") (pin "8") (pinfunction "LO_8") (pintype "output"))
    )
    (net (code "24") (name "Net-(U2-HB)") (class "Default")
      (node (ref "Cb2") (pin "1") (pinfunction "1_1") (pintype "passive"))
      (node (ref "U2") (pin "2") (pinfunction "HB_2") (pintype "power_in"))
    )
    (net (code "25") (name "Net-(U2-HI)") (class "Default")
      (node (ref "CN2") (pin "2") (pinfunction "2_2") (pintype "passive"))
      (node (ref "U2") (pin "5") (pinfunction "HI_5") (pintype "input"))
    )
    (net (code "26") (name "Net-(U2-HO)") (class "Default")
      (node (ref "R3") (pin "1") (pinfunction "1_1") (pintype "passive"))
      (node (ref "U2") (pin "3") (pinfunction "HO_3") (pintype "output"))
    )
    (net (code "27") (name "Net-(U2-LI)") (class "Default")
      (node (ref "CN2") (pin "3") (pinfunction "3_3") (pintype "passive"))
      (node (ref "U2") (pin "6") (pinfunction "LI_6") (pintype "input"))
    )
    (net (code "28") (name "Net-(U2-LO)") (class "Default")
      (node (ref "R9") (pin "1") (pinfunction "1_1") (pintype "passive"))
      (node (ref "U2") (pin "8") (pinfunction "LO_8") (pintype "output"))
    )
    (net (code "29") (name "Net-(U3-HB)") (class "Default")
      (node (ref "Cb3") (pin "1") (pinfunction "1_1") (pintype "passive"))
      (node (ref "U3") (pin "2") (pinfunction "HB_2") (pintype "power_in"))
    )
    (net (code "30") (name "Net-(U3-HI)") (class "Default")
      (node (ref "CN3") (pin "2") (pinfunction "2_2") (pintype "passive"))
      (node (ref "U3") (pin "5") (pinfunction "HI_5") (pintype "input"))
    )
    (net (code "31") (name "Net-(U3-HO)") (class "Default")
      (node (ref "R5") (pin "1") (pinfunction "1_1") (pintype "passive"))
      (node (ref "U3") (pin "3") (pinfunction "HO_3") (pintype "output"))
    )
    (net (code "32") (name "Net-(U3-LI)") (class "Default")
      (node (ref "CN3") (pin "3") (pinfunction "3_3") (pintype "passive"))
      (node (ref "U3") (pin "6") (pinfunction "LI_6") (pintype "input"))
    )
    (net (code "33") (name "Net-(U3-LO)") (class "Default")
      (node (ref "R7") (pin "1") (pinfunction "1_1") (pintype "passive"))
      (node (ref "U3") (pin "8") (pinfunction "LO_8") (pintype "output"))
    )
    (net (code "34") (name "unconnected-(CN1-Pad4)") (class "Default")
      (node (ref "CN1") (pin "4") (pinfunction "4_4") (pintype "passive+no_connect"))
    )
    (net (code "35") (name "unconnected-(CN1-PadMP1)") (class "Default")
      (node (ref "CN1") (pin "MP1") (pinfunction "MP1_MP1") (pintype "passive+no_connect"))
    )
    (net (code "36") (name "unconnected-(CN1-PadMP2)") (class "Default")
      (node (ref "CN1") (pin "MP2") (pinfunction "MP2_MP2") (pintype "passive+no_connect"))
    )
    (net (code "37") (name "unconnected-(CN2-Pad4)") (class "Default")
      (node (ref "CN2") (pin "4") (pinfunction "4_4") (pintype "passive+no_connect"))
    )
    (net (code "38") (name "unconnected-(CN2-PadMP1)") (class "Default")
      (node (ref "CN2") (pin "MP1") (pinfunction "MP1_MP1") (pintype "passive+no_connect"))
    )
    (net (code "39") (name "unconnected-(CN2-PadMP2)") (class "Default")
      (node (ref "CN2") (pin "MP2") (pinfunction "MP2_MP2") (pintype "passive+no_connect"))
    )
    (net (code "40") (name "unconnected-(CN3-Pad4)") (class "Default")
      (node (ref "CN3") (pin "4") (pinfunction "4_4") (pintype "passive+no_connect"))
    )
    (net (code "41") (name "unconnected-(CN3-PadMP1)") (class "Default")
      (node (ref "CN3") (pin "MP1") (pinfunction "MP1_MP1") (pintype "passive+no_connect"))
    )
    (net (code "42") (name "unconnected-(CN3-PadMP2)") (class "Default")
      (node (ref "CN3") (pin "MP2") (pinfunction "MP2_MP2") (pintype "passive+no_connect"))
    )
    (net (code "43") (name "unconnected-(LC-MNT_1-Pad4)") (class "Default")
      (node (ref "LC") (pin "4") (pinfunction "MNT_1_4") (pintype "passive+no_connect"))
    )
    (net (code "44") (name "unconnected-(LC-MNT_2-Pad5)") (class "Default")
      (node (ref "LC") (pin "5") (pinfunction "MNT_2_5") (pintype "passive+no_connect"))
    )
  )
)
